# Segger_TypeC_DebugBoard_v1.net
KiCad netlist of a schematic drawn in Altium Designer
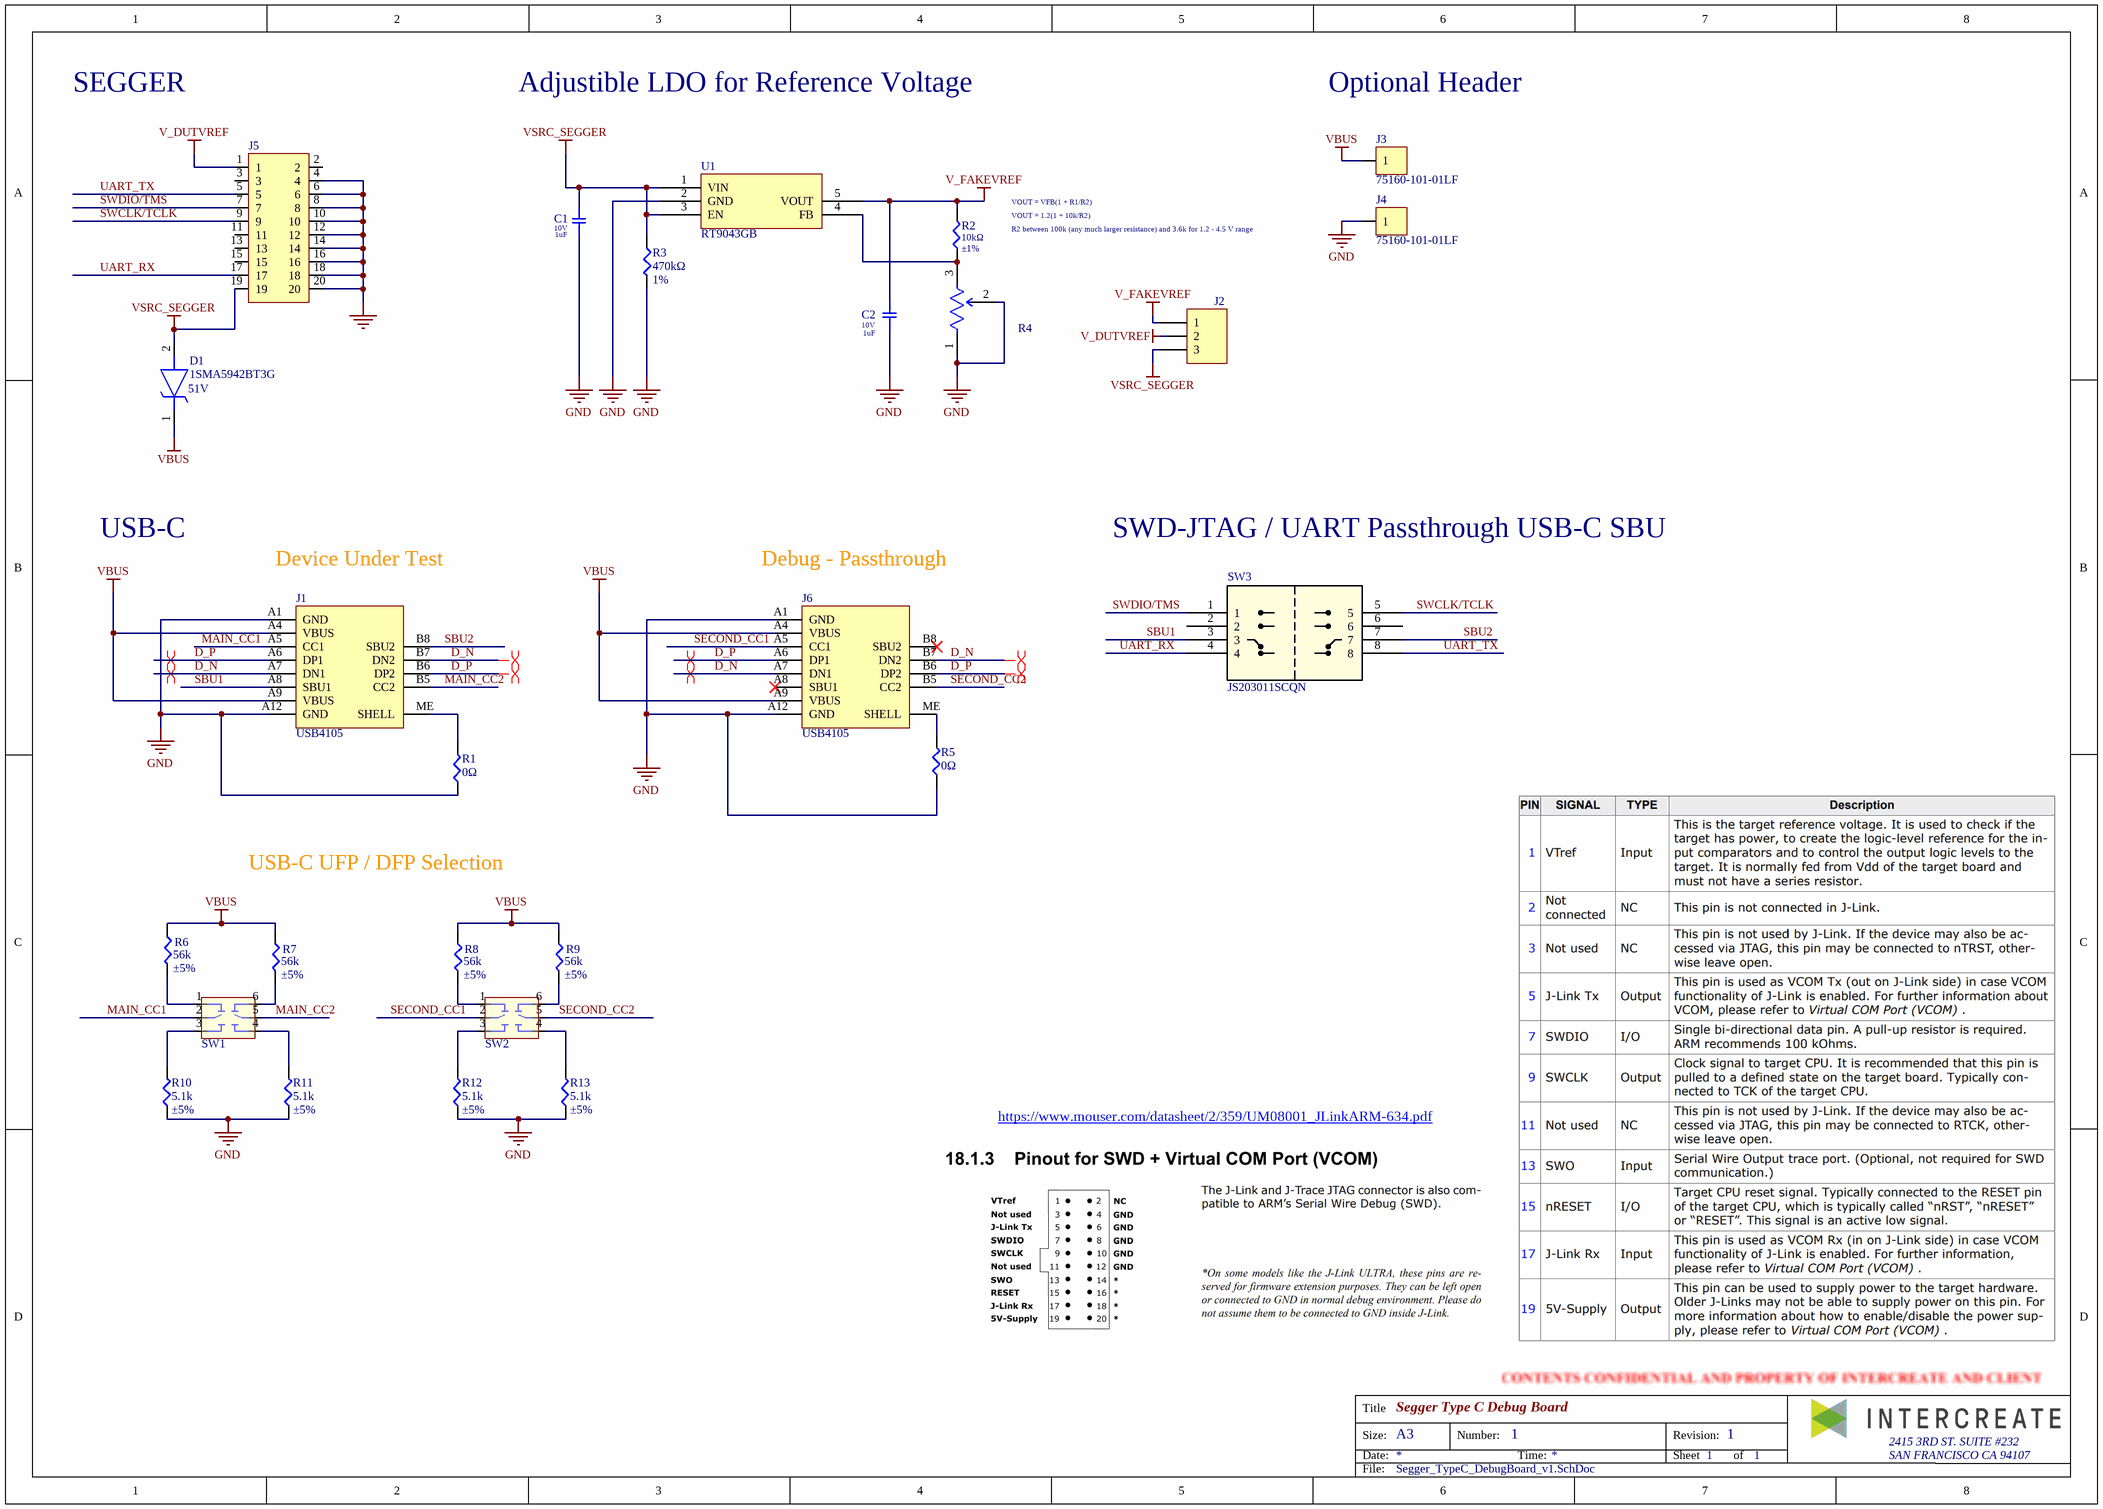
[diagram p0: Segger_TypeC_DebugBoard_v1.SchDoc]

(export (version "E")
  (design (tool "Eeschema 10.0.6"))
  (components
    (comp (ref "C1")
      (value "0402ZD105KAT2A")
      (footprint "CAP-0402")
      (fields
        (field (name "TOLERANCE") "10%")
        (field (name "VOLTAGE") "10V")
        (field (name "VOLTAGE RATING") "10V")
        (field (name "CAPACITANCE") "1uF")
      )
      (libsource (lib "intercreate") (part "CAP-1uF-10V-0402"))
    )
    (comp (ref "C2")
      (value "0402ZD105KAT2A")
      (footprint "CAP-0402")
      (fields
        (field (name "TOLERANCE") "10%")
        (field (name "VOLTAGE") "10V")
        (field (name "VOLTAGE RATING") "10V")
        (field (name "CAPACITANCE") "1uF")
      )
      (libsource (lib "intercreate") (part "CAP-1uF-10V-0402"))
    )
    (comp (ref "D1")
      (value "1SMA5942BT3G")
      (footprint "DIODE-SMA2")
      (description "Zener Diode 51 V 1.5 W ±5% Surface Mount SMA")
      (fields (field (name "ZENER VOLTAGE") "51V"))
      (libsource (lib "intercreate") (part "DIODE-ZNR-51V-SMA2"))
    )
    (comp (ref "J1")
      (value "USB4105")
      (footprint "CONN-USBC-GCT_USB4105")
      (description "Usb Conn, 2.0 Type C, Rcpt, 16Pos, Smt Rohs Compliant: Yes")
      (libsource (lib "intercreate") (part "CONN-F-USB-C-GCT_USB4105"))
    )
    (comp (ref "J2")
      (value "61300311121")
      (footprint "HDR-V-1X3")
      (description "Header, 3-Pin, 0.1\"")
      (fields (field (name "MANUFACTURER") "Wurth Electronics") (field (name "PUBLISHER") "Altium Limited"))
      (libsource (lib "intercreate") (part "HDR-V-1X3-M"))
    )
    (comp (ref "J3")
      (value "75160-101-01LF")
      (footprint "HDR-V-1X1-M")
      (libsource (lib "intercreate") (part "HDR-V-1X1-M"))
    )
    (comp (ref "J4")
      (value "75160-101-01LF")
      (footprint "HDR-V-1X1-M")
      (libsource (lib "intercreate") (part "HDR-V-1X1-M"))
    )
    (comp (ref "J5")
      (value "SFH11-PBPC-D10-ST-BK")
      (footprint "HDR-V-2X10-F-2.54MM")
      (description "20 Position Header Connector 0.100\" (2.54mm) Through Hole Gold")
      (libsource (lib "intercreate") (part "HDR-V-2X10-F-2.54MM"))
    )
    (comp (ref "J6")
      (value "USB4105")
      (footprint "CONN-USBC-GCT_USB4105")
      (description "Usb Conn, 2.0 Type C, Rcpt, 16Pos, Smt Rohs Compliant: Yes")
      (libsource (lib "intercreate") (part "CONN-F-USB-C-GCT_USB4105"))
    )
    (comp (ref "R1")
      (value "0Ω")
      (footprint "RES-0402")
      (description "RES 0 OHM JUMPER 1/16W 0402")
      (fields
        (field (name "MANUFACTURER") "Yageo")
        (field (name "MANUFACTURER PART NUMBER") "RC0402FR-070RL")
      )
      (libsource (lib "intercreate") (part "RES-0-0402"))
    )
    (comp (ref "R2")
      (value "10kΩ")
      (footprint "RES-0402")
      (description "RES SMD 10K OHM 1% 1/16W 0402")
      (fields (field (name "TOLERANCE") "±1%") (field (name "Comment") "RC0402FR-0710KL"))
      (libsource (lib "intercreate") (part "RES-10K-0402"))
    )
    (comp (ref "R3")
      (value "470kΩ")
      (footprint "RES-0402")
      (description "RES SMD 470K OHM 1% 1/16W 0402")
      (fields
        (field (name "TOLERANCE") "1%")
        (field (name "RESISTANCE TOLERANCE") "1%")
        (field (name "Comment") "RC0402FR-07470KL")
      )
      (libsource (lib "intercreate") (part "RES-470K-0402"))
    )
    (comp (ref "R4")
      (value "POT-ROT-100K-SMD")
      (footprint "3361P-1-104GLF")
      (description "TRIMMER 100K OHM 0.5W GW TOP ADJ")
      (libsource (lib "intercreate") (part "POT-ROT-100K-SMD"))
    )
    (comp (ref "R5")
      (value "0Ω")
      (footprint "RES-0402")
      (description "RES 0 OHM JUMPER 1/16W 0402")
      (fields
        (field (name "MANUFACTURER") "Yageo")
        (field (name "MANUFACTURER PART NUMBER") "RC0402FR-070RL")
      )
      (libsource (lib "intercreate") (part "RES-0-0402"))
    )
    (comp (ref "R6")
      (value "56k")
      (footprint "RES-0402")
      (description "RES SMD 56K OHM 5% 1/10W 0402")
      (fields (field (name "TOLERANCE") "±5%") (field (name "Comment") "ERJ2GEJ563X"))
      (libsource (lib "intercreate") (part "RES-56K-0402-5%"))
    )
    (comp (ref "R7")
      (value "56k")
      (footprint "RES-0402")
      (description "RES SMD 56K OHM 5% 1/10W 0402")
      (fields (field (name "TOLERANCE") "±5%") (field (name "Comment") "ERJ2GEJ563X"))
      (libsource (lib "intercreate") (part "RES-56K-0402-5%"))
    )
    (comp (ref "R8")
      (value "56k")
      (footprint "RES-0402")
      (description "RES SMD 56K OHM 5% 1/10W 0402")
      (fields (field (name "TOLERANCE") "±5%") (field (name "Comment") "ERJ2GEJ563X"))
      (libsource (lib "intercreate") (part "RES-56K-0402-5%"))
    )
    (comp (ref "R9")
      (value "56k")
      (footprint "RES-0402")
      (description "RES SMD 56K OHM 5% 1/10W 0402")
      (fields (field (name "TOLERANCE") "±5%") (field (name "Comment") "ERJ2GEJ563X"))
      (libsource (lib "intercreate") (part "RES-56K-0402-5%"))
    )
    (comp (ref "R10")
      (value "5.1k")
      (footprint "RES-0402")
      (description "RES SMD 5.1K OHM 5% 1/10W 0402")
      (fields (field (name "TOLERANCE") "±5%") (field (name "Comment") "ERJ2GEJ512X"))
      (libsource (lib "intercreate") (part "RES-5.1K-0402"))
    )
    (comp (ref "R11")
      (value "5.1k")
      (footprint "RES-0402")
      (description "RES SMD 5.1K OHM 5% 1/10W 0402")
      (fields (field (name "TOLERANCE") "±5%") (field (name "Comment") "ERJ2GEJ512X"))
      (libsource (lib "intercreate") (part "RES-5.1K-0402"))
    )
    (comp (ref "R12")
      (value "5.1k")
      (footprint "RES-0402")
      (description "RES SMD 5.1K OHM 5% 1/10W 0402")
      (fields (field (name "TOLERANCE") "±5%") (field (name "Comment") "ERJ2GEJ512X"))
      (libsource (lib "intercreate") (part "RES-5.1K-0402"))
    )
    (comp (ref "R13")
      (value "5.1k")
      (footprint "RES-0402")
      (description "RES SMD 5.1K OHM 5% 1/10W 0402")
      (fields (field (name "TOLERANCE") "±5%") (field (name "Comment") "ERJ2GEJ512X"))
      (libsource (lib "intercreate") (part "RES-5.1K-0402"))
    )
    (comp (ref "SW1")
      (value "CS-4-22YTA")
      (footprint "SW-BCD-CS-4-22YTA")
      (description "SWITCH ROTARY DIP DPDT 100MA 16V")
      (fields (field (name "MANUFACTURER") "Nidec Copal"))
      (libsource (lib "intercreate") (part "SW-DPDT-3P-ROTARY"))
    )
    (comp (ref "SW2")
      (value "CS-4-22YTA")
      (footprint "SW-BCD-CS-4-22YTA")
      (description "SWITCH ROTARY DIP DPDT 100MA 16V")
      (fields (field (name "MANUFACTURER") "Nidec Copal"))
      (libsource (lib "intercreate") (part "SW-DPDT-3P-ROTARY"))
    )
    (comp (ref "SW3")
      (value "JS203011SCQN")
      (footprint "SW-2P3T-SMD")
      (description "SWITCH SLIDE DP3T 300MA 6V")
      (libsource (lib "jlam") (part "SW-2P3T-SMD"))
    )
    (comp (ref "U1")
      (value "RT9043GB")
      (footprint "SOT-23-5")
      (description "IC REG LINEAR 3.3V 400mA SOT23-5")
      (libsource (lib "intercreate") (part "IC-PWR-LDO-RT9043GB"))
    )
  )
  (nets
    (net (code "1") (name "/D_N") (class "Default")
      (node (ref "J1") (pin "A7") (pinfunction "DN1_A7") (pintype "passive"))
      (node (ref "J1") (pin "B7") (pinfunction "DN2_B7") (pintype "passive"))
      (node (ref "J6") (pin "A7") (pinfunction "DN1_A7") (pintype "passive"))
      (node (ref "J6") (pin "B7") (pinfunction "DN2_B7") (pintype "passive"))
    )
    (net (code "2") (name "/D_P") (class "Default")
      (node (ref "J1") (pin "A6") (pinfunction "DP1_A6") (pintype "passive"))
      (node (ref "J1") (pin "B6") (pinfunction "DP2_B6") (pintype "passive"))
      (node (ref "J6") (pin "A6") (pinfunction "DP1_A6") (pintype "passive"))
      (node (ref "J6") (pin "B6") (pinfunction "DP2_B6") (pintype "passive"))
    )
    (net (code "3") (name "/MAIN_CC1") (class "Default")
      (node (ref "J1") (pin "A5") (pinfunction "CC1_A5") (pintype "passive"))
      (node (ref "SW1") (pin "2") (pinfunction "2_2") (pintype "passive"))
    )
    (net (code "4") (name "/MAIN_CC2") (class "Default")
      (node (ref "J1") (pin "B5") (pinfunction "CC2_B5") (pintype "passive"))
      (node (ref "SW1") (pin "5") (pinfunction "5_5") (pintype "passive"))
    )
    (net (code "5") (name "/SBU1") (class "Default")
      (node (ref "J1") (pin "A8") (pinfunction "SBU1_A8") (pintype "passive"))
      (node (ref "SW3") (pin "3") (pinfunction "3_3") (pintype "passive"))
    )
    (net (code "6") (name "/SBU2") (class "Default")
      (node (ref "J1") (pin "B8") (pinfunction "SBU2_B8") (pintype "passive"))
      (node (ref "SW3") (pin "7") (pinfunction "7_7") (pintype "passive"))
    )
    (net (code "7") (name "/SECOND_CC1") (class "Default")
      (node (ref "J6") (pin "A5") (pinfunction "CC1_A5") (pintype "passive"))
      (node (ref "SW2") (pin "2") (pinfunction "2_2") (pintype "passive"))
    )
    (net (code "8") (name "/SECOND_CC2") (class "Default")
      (node (ref "J6") (pin "B5") (pinfunction "CC2_B5") (pintype "passive"))
      (node (ref "SW2") (pin "5") (pinfunction "5_5") (pintype "passive"))
    )
    (net (code "9") (name "/SWCLK{slash}TCLK") (class "Default")
      (node (ref "J5") (pin "9") (pinfunction "9_9") (pintype "passive"))
      (node (ref "SW3") (pin "5") (pinfunction "5_5") (pintype "passive"))
    )
    (net (code "10") (name "/SWDIO{slash}TMS") (class "Default")
      (node (ref "J5") (pin "7") (pinfunction "7_7") (pintype "passive"))
      (node (ref "SW3") (pin "1") (pinfunction "1_1") (pintype "passive"))
    )
    (net (code "11") (name "/UART_RX") (class "Default")
      (node (ref "J5") (pin "17") (pinfunction "17_17") (pintype "passive"))
      (node (ref "SW3") (pin "4") (pinfunction "4_4") (pintype "passive"))
    )
    (net (code "12") (name "/UART_TX") (class "Default")
      (node (ref "J5") (pin "5") (pinfunction "5_5") (pintype "passive"))
      (node (ref "SW3") (pin "8") (pinfunction "8_8") (pintype "passive"))
    )
    (net (code "13") (name "GND") (class "Default")
      (node (ref "C1") (pin "1") (pinfunction "1_1") (pintype "passive"))
      (node (ref "C2") (pin "1") (pinfunction "1_1") (pintype "passive"))
      (node (ref "J1") (pin "A1") (pinfunction "GND_A1") (pintype "passive"))
      (node (ref "J1") (pin "A12") (pinfunction "GND_A12") (pintype "passive"))
      (node (ref "J4") (pin "1") (pinfunction "1_1") (pintype "passive"))
      (node (ref "J5") (pin "10") (pinfunction "10_10") (pintype "passive"))
      (node (ref "J5") (pin "12") (pinfunction "12_12") (pintype "passive"))
      (node (ref "J5") (pin "14") (pinfunction "14_14") (pintype "passive"))
      (node (ref "J5") (pin "16") (pinfunction "16_16") (pintype "passive"))
      (node (ref "J5") (pin "18") (pinfunction "18_18") (pintype "passive"))
      (node (ref "J5") (pin "20") (pinfunction "20_20") (pintype "passive"))
      (node (ref "J5") (pin "4") (pinfunction "4_4") (pintype "passive"))
      (node (ref "J5") (pin "6") (pinfunction "6_6") (pintype "passive"))
      (node (ref "J5") (pin "8") (pinfunction "8_8") (pintype "passive"))
      (node (ref "J6") (pin "A1") (pinfunction "GND_A1") (pintype "passive"))
      (node (ref "J6") (pin "A12") (pinfunction "GND_A12") (pintype "passive"))
      (node (ref "R1") (pin "1") (pinfunction "1_1") (pintype "passive"))
      (node (ref "R10") (pin "1") (pinfunction "1_1") (pintype "passive"))
      (node (ref "R11") (pin "1") (pinfunction "1_1") (pintype "passive"))
      (node (ref "R12") (pin "1") (pinfunction "1_1") (pintype "passive"))
      (node (ref "R13") (pin "1") (pinfunction "1_1") (pintype "passive"))
      (node (ref "R3") (pin "2") (pinfunction "2_2") (pintype "passive"))
      (node (ref "R4") (pin "1") (pinfunction "CCW_1") (pintype "passive"))
      (node (ref "R4") (pin "2") (pinfunction "WIPER_2") (pintype "passive"))
      (node (ref "R5") (pin "1") (pinfunction "1_1") (pintype "passive"))
      (node (ref "U1") (pin "2") (pinfunction "GND_2") (pintype "passive"))
    )
    (net (code "14") (name "Net-(J1-SHELL)") (class "Default")
      (node (ref "J1") (pin "ME") (pinfunction "SHELL_ME") (pintype "passive"))
      (node (ref "R1") (pin "2") (pinfunction "2_2") (pintype "passive"))
    )
    (net (code "15") (name "Net-(J6-SHELL)") (class "Default")
      (node (ref "J6") (pin "ME") (pinfunction "SHELL_ME") (pintype "passive"))
      (node (ref "R5") (pin "2") (pinfunction "2_2") (pintype "passive"))
    )
    (net (code "16") (name "Net-(R4-CW)") (class "Default")
      (node (ref "R2") (pin "1") (pinfunction "1_1") (pintype "passive"))
      (node (ref "R4") (pin "3") (pinfunction "CW_3") (pintype "passive"))
      (node (ref "U1") (pin "4") (pinfunction "FB_4") (pintype "passive"))
    )
    (net (code "17") (name "Net-(R6-Pad2)") (class "Default")
      (node (ref "R6") (pin "2") (pinfunction "2_2") (pintype "passive"))
      (node (ref "SW1") (pin "1") (pinfunction "1_1") (pintype "passive"))
    )
    (net (code "18") (name "Net-(R7-Pad2)") (class "Default")
      (node (ref "R7") (pin "2") (pinfunction "2_2") (pintype "passive"))
      (node (ref "SW1") (pin "6") (pinfunction "6_6") (pintype "passive"))
    )
    (net (code "19") (name "Net-(R8-Pad2)") (class "Default")
      (node (ref "R8") (pin "2") (pinfunction "2_2") (pintype "passive"))
      (node (ref "SW2") (pin "1") (pinfunction "1_1") (pintype "passive"))
    )
    (net (code "20") (name "Net-(R9-Pad2)") (class "Default")
      (node (ref "R9") (pin "2") (pinfunction "2_2") (pintype "passive"))
      (node (ref "SW2") (pin "6") (pinfunction "6_6") (pintype "passive"))
    )
    (net (code "21") (name "Net-(R10-Pad2)") (class "Default")
      (node (ref "R10") (pin "2") (pinfunction "2_2") (pintype "passive"))
      (node (ref "SW1") (pin "3") (pinfunction "3_3") (pintype "passive"))
    )
    (net (code "22") (name "Net-(R11-Pad2)") (class "Default")
      (node (ref "R11") (pin "2") (pinfunction "2_2") (pintype "passive"))
      (node (ref "SW1") (pin "4") (pinfunction "4_4") (pintype "passive"))
    )
    (net (code "23") (name "Net-(R12-Pad2)") (class "Default")
      (node (ref "R12") (pin "2") (pinfunction "2_2") (pintype "passive"))
      (node (ref "SW2") (pin "3") (pinfunction "3_3") (pintype "passive"))
    )
    (net (code "24") (name "Net-(R13-Pad2)") (class "Default")
      (node (ref "R13") (pin "2") (pinfunction "2_2") (pintype "passive"))
      (node (ref "SW2") (pin "4") (pinfunction "4_4") (pintype "passive"))
    )
    (net (code "25") (name "VBUS") (class "Default")
      (node (ref "D1") (pin "1") (pinfunction "K_1") (pintype "passive"))
      (node (ref "J1") (pin "A4") (pinfunction "VBUS_A4") (pintype "passive"))
      (node (ref "J1") (pin "A9") (pinfunction "VBUS_A9") (pintype "passive"))
      (node (ref "J3") (pin "1") (pinfunction "1_1") (pintype "passive"))
      (node (ref "J6") (pin "A4") (pinfunction "VBUS_A4") (pintype "passive"))
      (node (ref "J6") (pin "A9") (pinfunction "VBUS_A9") (pintype "passive"))
      (node (ref "R6") (pin "1") (pinfunction "1_1") (pintype "passive"))
      (node (ref "R7") (pin "1") (pinfunction "1_1") (pintype "passive"))
      (node (ref "R8") (pin "1") (pinfunction "1_1") (pintype "passive"))
      (node (ref "R9") (pin "1") (pinfunction "1_1") (pintype "passive"))
    )
    (net (code "26") (name "VSRC_SEGGER") (class "Default")
      (node (ref "C1") (pin "2") (pinfunction "2_2") (pintype "passive"))
      (node (ref "D1") (pin "2") (pinfunction "A_2") (pintype "passive"))
      (node (ref "J2") (pin "3") (pinfunction "3_3") (pintype "passive"))
      (node (ref "J5") (pin "19") (pinfunction "19_19") (pintype "passive"))
      (node (ref "R3") (pin "1") (pinfunction "1_1") (pintype "passive"))
      (node (ref "U1") (pin "1") (pinfunction "VIN_1") (pintype "passive"))
      (node (ref "U1") (pin "3") (pinfunction "EN_3") (pintype "passive"))
    )
    (net (code "27") (name "V_DUTVREF") (class "Default")
      (node (ref "J2") (pin "2") (pinfunction "2_2") (pintype "passive"))
      (node (ref "J5") (pin "1") (pinfunction "1_1") (pintype "passive"))
    )
    (net (code "28") (name "V_FAKEVREF") (class "Default")
      (node (ref "C2") (pin "2") (pinfunction "2_2") (pintype "passive"))
      (node (ref "J2") (pin "1") (pinfunction "1_1") (pintype "passive"))
      (node (ref "R2") (pin "2") (pinfunction "2_2") (pintype "passive"))
      (node (ref "U1") (pin "5") (pinfunction "VOUT_5") (pintype "passive"))
    )
    (net (code "29") (name "unconnected-(J5-Pad2)") (class "Default")
      (node (ref "J5") (pin "2") (pinfunction "2_2") (pintype "passive"))
    )
    (net (code "30") (name "unconnected-(J5-Pad3)") (class "Default")
      (node (ref "J5") (pin "3") (pinfunction "3_3") (pintype "passive"))
    )
    (net (code "31") (name "unconnected-(J5-Pad11)") (class "Default")
      (node (ref "J5") (pin "11") (pinfunction "11_11") (pintype "passive"))
    )
    (net (code "32") (name "unconnected-(J5-Pad13)") (class "Default")
      (node (ref "J5") (pin "13") (pinfunction "13_13") (pintype "passive"))
    )
    (net (code "33") (name "unconnected-(J5-Pad15)") (class "Default")
      (node (ref "J5") (pin "15") (pinfunction "15_15") (pintype "passive"))
    )
    (net (code "34") (name "unconnected-(J6-SBU1-PadA8)") (class "Default")
      (node (ref "J6") (pin "A8") (pinfunction "SBU1_A8") (pintype "passive+no_connect"))
    )
    (net (code "35") (name "unconnected-(J6-SBU2-PadB8)") (class "Default")
      (node (ref "J6") (pin "B8") (pinfunction "SBU2_B8") (pintype "passive+no_connect"))
    )
    (net (code "36") (name "unconnected-(SW3-Pad2)") (class "Default")
      (node (ref "SW3") (pin "2") (pinfunction "2_2") (pintype "passive"))
    )
    (net (code "37") (name "unconnected-(SW3-Pad6)") (class "Default")
      (node (ref "SW3") (pin "6") (pinfunction "6_6") (pintype "passive"))
    )
  )
)
